# LED.net
KiCad netlist of a schematic drawn in Altium Designer
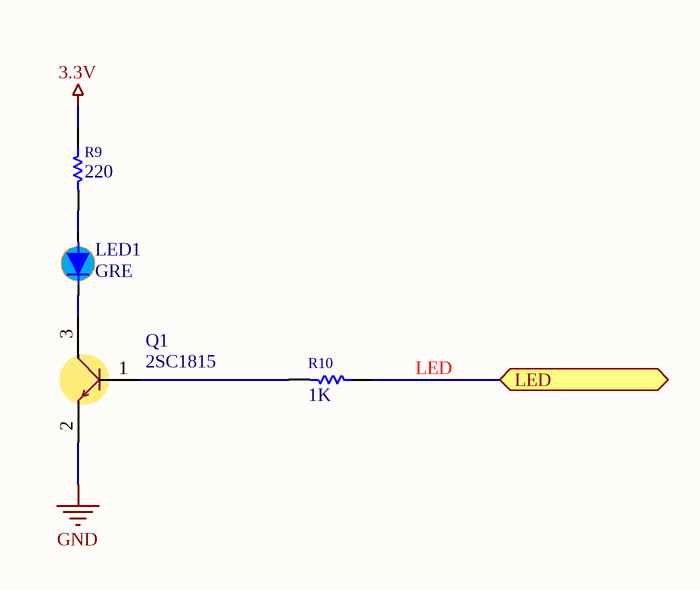
[diagram p0: LED.SchDoc]

(export (version "E")
  (design (tool "Eeschema 10.0.6"))
  (components
    (comp (ref "LED1") (value "GRE") (footprint "Led 3mm_D") (libsource (lib "LIB_Altium2020") (part "Led")))
    (comp (ref "Q1")
      (value "2SC1815")
      (footprint "SOT23")
      (description "SMD TRANSISTOR")
      (libsource (lib "LIB_Altium2020") (part "NPN_SMD"))
    )
    (comp (ref "R9")
      (value "220")
      (footprint "R2012-0805")
      (description "Resistor")
      (fields (field (name "PUBLISHER") "Hoang Nguyen"))
      (libsource (lib "LIB_Altium2020") (part "Resistor {lt}SMD{gt}"))
    )
    (comp (ref "R10")
      (value "1K")
      (footprint "R2012-0805")
      (description "Resistor")
      (fields (field (name "PUBLISHER") "Hoang Nguyen"))
      (libsource (lib "LIB_Altium2020") (part "Resistor {lt}SMD{gt}"))
    )
  )
  (nets
    (net (code "1") (name "/LED") (class "Default")
      (node (ref "R10") (pin "1") (pinfunction "1_1") (pintype "passive"))
    )
    (net (code "2") (name "3.3V") (class "Default")
      (node (ref "R9") (pin "1") (pinfunction "1_1") (pintype "passive"))
    )
    (net (code "3") (name "GND") (class "Default")
      (node (ref "Q1") (pin "2") (pinfunction "E_2") (pintype "passive"))
    )
    (net (code "4") (name "Net-(LED1-A)") (class "Default")
      (node (ref "LED1") (pin "1") (pinfunction "A_1") (pintype "passive"))
      (node (ref "R9") (pin "2") (pinfunction "2_2") (pintype "passive"))
    )
    (net (code "5") (name "Net-(LED1-K)") (class "Default")
      (node (ref "LED1") (pin "2") (pinfunction "K_2") (pintype "passive"))
      (node (ref "Q1") (pin "3") (pinfunction "C_3") (pintype "passive"))
    )
    (net (code "6") (name "Net-(Q1-B)") (class "Default")
      (node (ref "Q1") (pin "1") (pinfunction "B_1") (pintype "passive"))
      (node (ref "R10") (pin "2") (pinfunction "2_2") (pintype "passive"))
    )
  )
)
